# Automotive_Inter_BoB.net
KiCad netlist of a schematic drawn in EAGLE
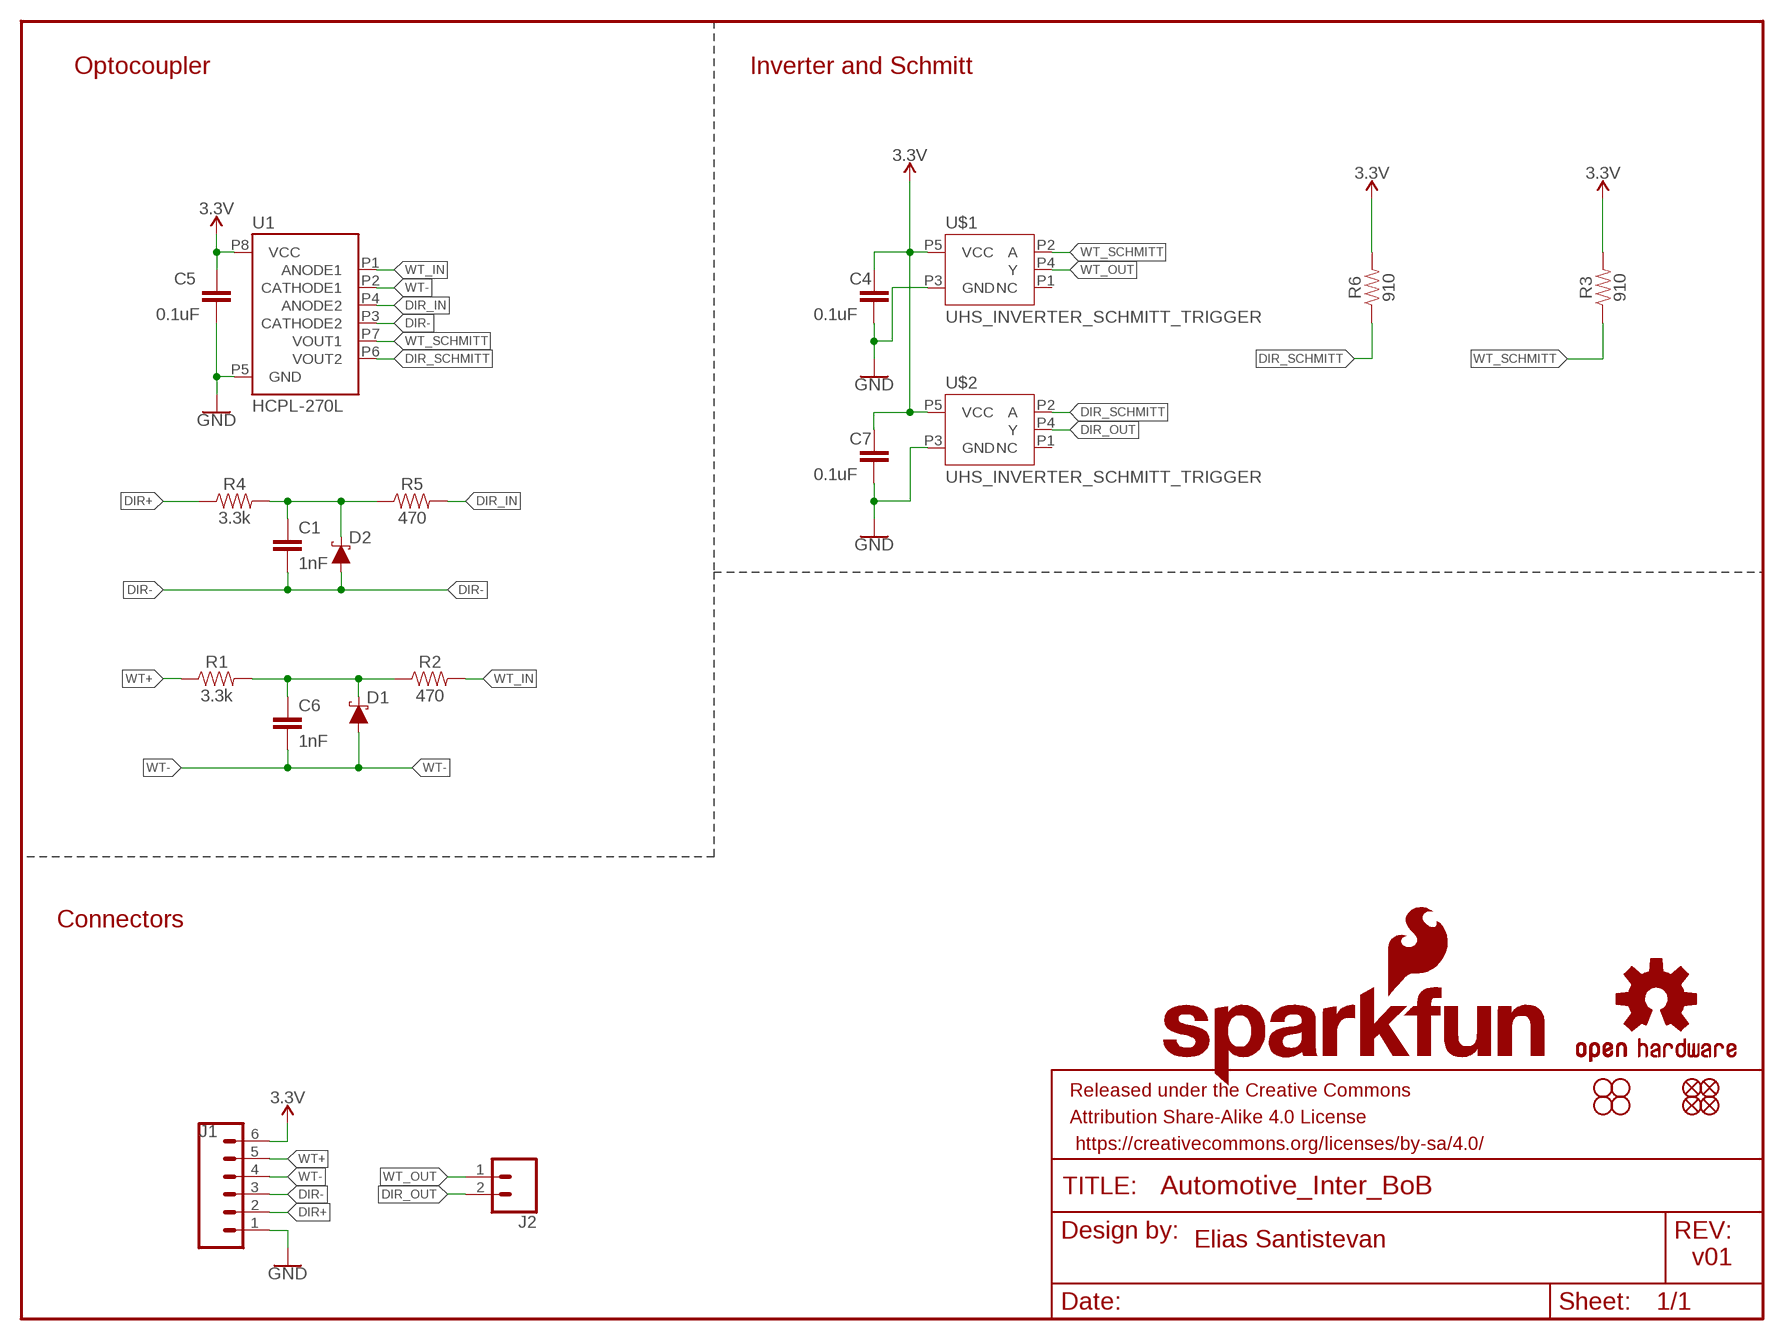
[diagram p0: schematic, sheet 1]

(export (version "E")
  (design (tool "Eeschema 10.0.6"))
  (components
    (comp (ref "C1")
      (value "1nF")
      (footprint "eagle-import:0603")
      (libsource (lib "eagle-import") (part "1.0NF/1000PF-0603-50V-10%"))
    )
    (comp (ref "C4")
      (value "0.1uF")
      (footprint "eagle-import:0603")
      (libsource (lib "eagle-import") (part "0.1UF-0603-100V-10%"))
    )
    (comp (ref "C5")
      (value "0.1uF")
      (footprint "eagle-import:0603")
      (libsource (lib "eagle-import") (part "0.1UF-0603-100V-10%"))
    )
    (comp (ref "C6")
      (value "1nF")
      (footprint "eagle-import:0603")
      (libsource (lib "eagle-import") (part "1.0NF/1000PF-0603-50V-10%"))
    )
    (comp (ref "C7")
      (value "0.1uF")
      (footprint "eagle-import:0603")
      (libsource (lib "eagle-import") (part "0.1UF-0603-100V-10%"))
    )
    (comp (ref "D1")
      (value "0.5A/40V/420mV")
      (footprint "eagle-import:SOD-323")
      (libsource (lib "eagle-import") (part "DIODE-SCHOTTKY-PMEG4005EJ"))
    )
    (comp (ref "D2")
      (value "0.5A/40V/420mV")
      (footprint "eagle-import:SOD-323")
      (libsource (lib "eagle-import") (part "DIODE-SCHOTTKY-PMEG4005EJ"))
    )
    (comp (ref "FD1")
      (value "FIDUCIALUFIDUCIAL")
      (footprint "eagle-import:FIDUCIAL-MICRO")
      (libsource (lib "eagle-import") (part "FIDUCIALUFIDUCIAL"))
    )
    (comp (ref "FD2")
      (value "FIDUCIALUFIDUCIAL")
      (footprint "eagle-import:FIDUCIAL-MICRO")
      (libsource (lib "eagle-import") (part "FIDUCIALUFIDUCIAL"))
    )
    (comp (ref "FD3")
      (value "FIDUCIALUFIDUCIAL")
      (footprint "eagle-import:FIDUCIAL-MICRO")
      (libsource (lib "eagle-import") (part "FIDUCIALUFIDUCIAL"))
    )
    (comp (ref "FD4")
      (value "FIDUCIALUFIDUCIAL")
      (footprint "eagle-import:FIDUCIAL-MICRO")
      (libsource (lib "eagle-import") (part "FIDUCIALUFIDUCIAL"))
    )
    (comp (ref "FRAME1")
      (value "FRAME-LETTER")
      (footprint "eagle-import:CREATIVE_COMMONS")
      (libsource (lib "eagle-import") (part "FRAME-LETTER"))
    )
    (comp (ref "H1")
      (value "STAND-OFF")
      (footprint "eagle-import:STAND-OFF")
      (libsource (lib "eagle-import") (part "STAND-OFF"))
    )
    (comp (ref "H2")
      (value "STAND-OFF")
      (footprint "eagle-import:STAND-OFF")
      (libsource (lib "eagle-import") (part "STAND-OFF"))
    )
    (comp (ref "H3")
      (value "STAND-OFF")
      (footprint "eagle-import:STAND-OFF")
      (libsource (lib "eagle-import") (part "STAND-OFF"))
    )
    (comp (ref "H4")
      (value "STAND-OFF")
      (footprint "eagle-import:STAND-OFF")
      (libsource (lib "eagle-import") (part "STAND-OFF"))
    )
    (comp (ref "J1")
      (value "CONN_06NO_SILK_NO_POP")
      (footprint "eagle-import:1X06_NO_SILK")
      (libsource (lib "eagle-import") (part "CONN_06NO_SILK_NO_POP"))
    )
    (comp (ref "J2")
      (value "CONN_021X02_NO_SILK")
      (footprint "eagle-import:1X02_NO_SILK")
      (libsource (lib "eagle-import") (part "CONN_021X02_NO_SILK"))
    )
    (comp (ref "LOGO1")
      (value "SFE_LOGO_NAME_FLAME.1_INCH")
      (footprint "eagle-import:SFE_LOGO_NAME_FLAME_.1")
      (libsource (lib "eagle-import") (part "SFE_LOGO_NAME_FLAME.1_INCH"))
    )
    (comp (ref "LOGO2")
      (value "OSHW-LOGOS")
      (footprint "eagle-import:OSHW-LOGO-S")
      (libsource (lib "eagle-import") (part "OSHW-LOGOS"))
    )
    (comp (ref "R1")
      (value "3.3k")
      (footprint "eagle-import:0603")
      (libsource (lib "eagle-import") (part "3.3KOHM-0603-1/10W-1%"))
    )
    (comp (ref "R2")
      (value "470")
      (footprint "eagle-import:0603")
      (libsource (lib "eagle-import") (part "470OHM-0603-1/10W-1%"))
    )
    (comp (ref "R3")
      (value "910")
      (footprint "eagle-import:0603")
      (libsource (lib "eagle-import") (part "910OHM-0603-1/10W-5%"))
    )
    (comp (ref "R4")
      (value "3.3k")
      (footprint "eagle-import:0603")
      (libsource (lib "eagle-import") (part "3.3KOHM-0603-1/10W-1%"))
    )
    (comp (ref "R5")
      (value "470")
      (footprint "eagle-import:0603")
      (libsource (lib "eagle-import") (part "470OHM-0603-1/10W-1%"))
    )
    (comp (ref "R6")
      (value "910")
      (footprint "eagle-import:0603")
      (libsource (lib "eagle-import") (part "910OHM-0603-1/10W-5%"))
    )
    (comp (ref "U$1")
      (value "UHS_INVERTER_SCHMITT_TRIGGER")
      (footprint "eagle-import:SC-74A")
      (libsource (lib "eagle-import") (part "UHS_INVERTER_SCHMITT_TRIGGER"))
    )
    (comp (ref "U$2")
      (value "UHS_INVERTER_SCHMITT_TRIGGER")
      (footprint "eagle-import:SC-74A")
      (libsource (lib "eagle-import") (part "UHS_INVERTER_SCHMITT_TRIGGER"))
    )
    (comp (ref "U1")
      (value "HCPL-270L")
      (footprint "eagle-import:SOP_8-PIN")
      (libsource (lib "eagle-import") (part "HCPL-270L"))
    )
  )
  (nets
    (net (code "1") (name "3.3V") (class "Default")
      (node (ref "C4") (pin "1") (pinfunction "1_1") (pintype "passive"))
      (node (ref "C5") (pin "1") (pinfunction "1_1") (pintype "passive"))
      (node (ref "C7") (pin "1") (pinfunction "1_1") (pintype "passive"))
      (node (ref "J1") (pin "6") (pinfunction "6_6") (pintype "passive"))
      (node (ref "R3") (pin "2") (pinfunction "2_2") (pintype "passive"))
      (node (ref "R6") (pin "2") (pinfunction "2_2") (pintype "passive"))
      (node (ref "U$1") (pin "P5") (pinfunction "VCC_P5") (pintype "power_in"))
      (node (ref "U$2") (pin "P5") (pinfunction "VCC_P5") (pintype "power_in"))
      (node (ref "U1") (pin "P8") (pinfunction "VCC_P8") (pintype "power_in"))
    )
    (net (code "2") (name "DIR+") (class "Default")
      (node (ref "J1") (pin "2") (pinfunction "2_2") (pintype "passive"))
      (node (ref "R4") (pin "1") (pinfunction "1_1") (pintype "passive"))
    )
    (net (code "3") (name "DIR-") (class "Default")
      (node (ref "C1") (pin "2") (pinfunction "2_2") (pintype "passive"))
      (node (ref "D2") (pin "A") (pinfunction "A_A") (pintype "passive"))
      (node (ref "J1") (pin "3") (pinfunction "3_3") (pintype "passive"))
      (node (ref "U1") (pin "P3") (pinfunction "CATHODE2_P3") (pintype "input"))
    )
    (net (code "4") (name "DIR_IN") (class "Default")
      (node (ref "R5") (pin "2") (pinfunction "2_2") (pintype "passive"))
      (node (ref "U1") (pin "P4") (pinfunction "ANODE2_P4") (pintype "input"))
    )
    (net (code "5") (name "DIR_OUT") (class "Default")
      (node (ref "J2") (pin "2") (pinfunction "2_2") (pintype "passive"))
      (node (ref "U$2") (pin "P4") (pinfunction "Y_P4") (pintype "bidirectional"))
    )
    (net (code "6") (name "DIR_SCHMITT") (class "Default")
      (node (ref "R6") (pin "1") (pinfunction "1_1") (pintype "passive"))
      (node (ref "U$2") (pin "P2") (pinfunction "A_P2") (pintype "bidirectional"))
      (node (ref "U1") (pin "P6") (pinfunction "VOUT2_P6") (pintype "output"))
    )
    (net (code "7") (name "GND") (class "Default")
      (node (ref "C4") (pin "2") (pinfunction "2_2") (pintype "passive"))
      (node (ref "C5") (pin "2") (pinfunction "2_2") (pintype "passive"))
      (node (ref "C7") (pin "2") (pinfunction "2_2") (pintype "passive"))
      (node (ref "J1") (pin "1") (pinfunction "1_1") (pintype "passive"))
      (node (ref "U$1") (pin "P3") (pinfunction "GND_P3") (pintype "power_in"))
      (node (ref "U$2") (pin "P3") (pinfunction "GND_P3") (pintype "power_in"))
      (node (ref "U1") (pin "P5") (pinfunction "GND_P5") (pintype "power_in"))
    )
    (net (code "8") (name "Net-(C1-Pad1)") (class "Default")
      (node (ref "C1") (pin "1") (pinfunction "1_1") (pintype "passive"))
      (node (ref "D2") (pin "C") (pinfunction "C_C") (pintype "passive"))
      (node (ref "R4") (pin "2") (pinfunction "2_2") (pintype "passive"))
      (node (ref "R5") (pin "1") (pinfunction "1_1") (pintype "passive"))
    )
    (net (code "9") (name "Net-(C6-Pad1)") (class "Default")
      (node (ref "C6") (pin "1") (pinfunction "1_1") (pintype "passive"))
      (node (ref "D1") (pin "C") (pinfunction "C_C") (pintype "passive"))
      (node (ref "R1") (pin "2") (pinfunction "2_2") (pintype "passive"))
      (node (ref "R2") (pin "1") (pinfunction "1_1") (pintype "passive"))
    )
    (net (code "10") (name "WT+") (class "Default")
      (node (ref "J1") (pin "5") (pinfunction "5_5") (pintype "passive"))
      (node (ref "R1") (pin "1") (pinfunction "1_1") (pintype "passive"))
    )
    (net (code "11") (name "WT-") (class "Default")
      (node (ref "C6") (pin "2") (pinfunction "2_2") (pintype "passive"))
      (node (ref "D1") (pin "A") (pinfunction "A_A") (pintype "passive"))
      (node (ref "J1") (pin "4") (pinfunction "4_4") (pintype "passive"))
      (node (ref "U1") (pin "P2") (pinfunction "CATHODE1_P2") (pintype "input"))
    )
    (net (code "12") (name "WT_IN") (class "Default")
      (node (ref "R2") (pin "2") (pinfunction "2_2") (pintype "passive"))
      (node (ref "U1") (pin "P1") (pinfunction "ANODE1_P1") (pintype "input"))
    )
    (net (code "13") (name "WT_OUT") (class "Default")
      (node (ref "J2") (pin "1") (pinfunction "1_1") (pintype "passive"))
      (node (ref "U$1") (pin "P4") (pinfunction "Y_P4") (pintype "bidirectional"))
    )
    (net (code "14") (name "WT_SCHMITT") (class "Default")
      (node (ref "R3") (pin "1") (pinfunction "1_1") (pintype "passive"))
      (node (ref "U$1") (pin "P2") (pinfunction "A_P2") (pintype "bidirectional"))
      (node (ref "U1") (pin "P7") (pinfunction "VOUT1_P7") (pintype "output"))
    )
    (net (code "15") (name "unconnected-(U$1-NC-PadP1)") (class "Default")
      (node (ref "U$1") (pin "P1") (pinfunction "NC_P1") (pintype "no_connect"))
    )
    (net (code "16") (name "unconnected-(U$2-NC-PadP1)") (class "Default")
      (node (ref "U$2") (pin "P1") (pinfunction "NC_P1") (pintype "no_connect"))
    )
  )
)
